# IGBT.net
KiCad netlist of a schematic drawn in Altium Designer
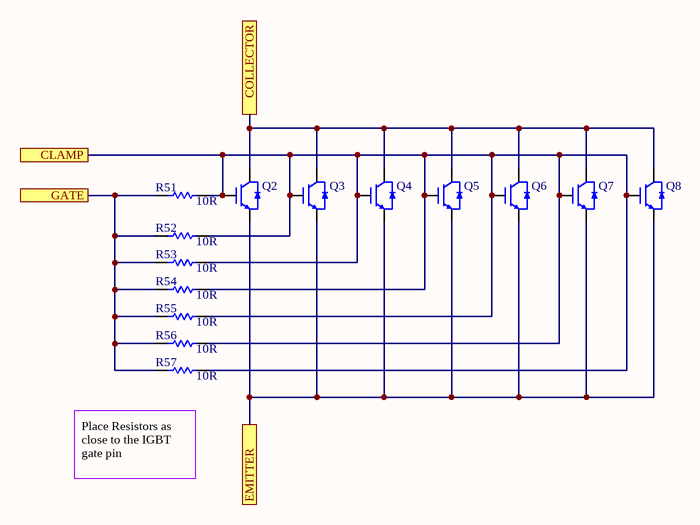
[diagram p0: IGBT.SchDoc]

(export (version "E")
  (design (tool "Eeschema 10.0.6"))
  (components
    (comp (ref "Q2")
      (value "STGB30V60DF")
      (footprint "DPAK2_IGBT")
      (description "IGBT 600V 60A 258W D2PAK")
      (fields (field (name "MANUFACTURER") "STMicroelectronics"))
      (libsource (lib "InverterSCHLib") (part "STGB30V60DF"))
    )
    (comp (ref "Q3")
      (value "STGB30V60DF")
      (footprint "DPAK2_IGBT")
      (description "IGBT 600V 60A 258W D2PAK")
      (fields (field (name "MANUFACTURER") "STMicroelectronics"))
      (libsource (lib "InverterSCHLib") (part "STGB30V60DF"))
    )
    (comp (ref "Q4")
      (value "STGB30V60DF")
      (footprint "DPAK2_IGBT")
      (description "IGBT 600V 60A 258W D2PAK")
      (fields (field (name "MANUFACTURER") "STMicroelectronics"))
      (libsource (lib "InverterSCHLib") (part "STGB30V60DF"))
    )
    (comp (ref "Q5")
      (value "STGB30V60DF")
      (footprint "DPAK2_IGBT")
      (description "IGBT 600V 60A 258W D2PAK")
      (fields (field (name "MANUFACTURER") "STMicroelectronics"))
      (libsource (lib "InverterSCHLib") (part "STGB30V60DF"))
    )
    (comp (ref "Q6")
      (value "STGB30V60DF")
      (footprint "DPAK2_IGBT")
      (description "IGBT 600V 60A 258W D2PAK")
      (fields (field (name "MANUFACTURER") "STMicroelectronics"))
      (libsource (lib "InverterSCHLib") (part "STGB30V60DF"))
    )
    (comp (ref "Q7")
      (value "STGB30V60DF")
      (footprint "DPAK2_IGBT")
      (description "IGBT 600V 60A 258W D2PAK")
      (fields (field (name "MANUFACTURER") "STMicroelectronics"))
      (libsource (lib "InverterSCHLib") (part "STGB30V60DF"))
    )
    (comp (ref "Q8")
      (value "STGB30V60DF")
      (footprint "DPAK2_IGBT")
      (description "IGBT 600V 60A 258W D2PAK")
      (fields (field (name "MANUFACTURER") "STMicroelectronics"))
      (libsource (lib "InverterSCHLib") (part "STGB30V60DF"))
    )
    (comp (ref "R51")
      (value "10R")
      (footprint "RES-0603")
      (description "RES SMD 10 OHM 1% 1/10W 0603")
      (fields
        (field (name "MANUFACTURER") "Yageo")
        (field (name "MANUFACTURER PART NUMBER") "RC0603FR-0710RL")
      )
      (libsource (lib "InverterSCHLib") (part "0603-10R"))
    )
    (comp (ref "R52")
      (value "10R")
      (footprint "RES-0603")
      (description "RES SMD 10 OHM 1% 1/10W 0603")
      (fields
        (field (name "MANUFACTURER") "Yageo")
        (field (name "MANUFACTURER PART NUMBER") "RC0603FR-0710RL")
      )
      (libsource (lib "InverterSCHLib") (part "0603-10R"))
    )
    (comp (ref "R53")
      (value "10R")
      (footprint "RES-0603")
      (description "RES SMD 10 OHM 1% 1/10W 0603")
      (fields
        (field (name "MANUFACTURER") "Yageo")
        (field (name "MANUFACTURER PART NUMBER") "RC0603FR-0710RL")
      )
      (libsource (lib "InverterSCHLib") (part "0603-10R"))
    )
    (comp (ref "R54")
      (value "10R")
      (footprint "RES-0603")
      (description "RES SMD 10 OHM 1% 1/10W 0603")
      (fields
        (field (name "MANUFACTURER") "Yageo")
        (field (name "MANUFACTURER PART NUMBER") "RC0603FR-0710RL")
      )
      (libsource (lib "InverterSCHLib") (part "0603-10R"))
    )
    (comp (ref "R55")
      (value "10R")
      (footprint "RES-0603")
      (description "RES SMD 10 OHM 1% 1/10W 0603")
      (fields
        (field (name "MANUFACTURER") "Yageo")
        (field (name "MANUFACTURER PART NUMBER") "RC0603FR-0710RL")
      )
      (libsource (lib "InverterSCHLib") (part "0603-10R"))
    )
    (comp (ref "R56")
      (value "10R")
      (footprint "RES-0603")
      (description "RES SMD 10 OHM 1% 1/10W 0603")
      (fields
        (field (name "MANUFACTURER") "Yageo")
        (field (name "MANUFACTURER PART NUMBER") "RC0603FR-0710RL")
      )
      (libsource (lib "InverterSCHLib") (part "0603-10R"))
    )
    (comp (ref "R57")
      (value "10R")
      (footprint "RES-0603")
      (description "RES SMD 10 OHM 1% 1/10W 0603")
      (fields
        (field (name "MANUFACTURER") "Yageo")
        (field (name "MANUFACTURER PART NUMBER") "RC0603FR-0710RL")
      )
      (libsource (lib "InverterSCHLib") (part "0603-10R"))
    )
  )
  (nets
    (net (code "1") (name "/CLAMP") (class "Default")
      (node (ref "Q2") (pin "1") (pinfunction "1_1") (pintype "passive"))
      (node (ref "Q3") (pin "1") (pinfunction "1_1") (pintype "passive"))
      (node (ref "Q4") (pin "1") (pinfunction "1_1") (pintype "passive"))
      (node (ref "Q5") (pin "1") (pinfunction "1_1") (pintype "passive"))
      (node (ref "Q6") (pin "1") (pinfunction "1_1") (pintype "passive"))
      (node (ref "Q7") (pin "1") (pinfunction "1_1") (pintype "passive"))
      (node (ref "Q8") (pin "1") (pinfunction "1_1") (pintype "passive"))
      (node (ref "R51") (pin "2") (pinfunction "2_2") (pintype "passive"))
      (node (ref "R52") (pin "2") (pinfunction "2_2") (pintype "passive"))
      (node (ref "R53") (pin "2") (pinfunction "2_2") (pintype "passive"))
      (node (ref "R54") (pin "2") (pinfunction "2_2") (pintype "passive"))
      (node (ref "R55") (pin "2") (pinfunction "2_2") (pintype "passive"))
      (node (ref "R56") (pin "2") (pinfunction "2_2") (pintype "passive"))
      (node (ref "R57") (pin "2") (pinfunction "2_2") (pintype "passive"))
    )
    (net (code "2") (name "/COLLECTOR") (class "Default")
      (node (ref "Q2") (pin "2") (pinfunction "2_2") (pintype "passive"))
      (node (ref "Q3") (pin "2") (pinfunction "2_2") (pintype "passive"))
      (node (ref "Q4") (pin "2") (pinfunction "2_2") (pintype "passive"))
      (node (ref "Q5") (pin "2") (pinfunction "2_2") (pintype "passive"))
      (node (ref "Q6") (pin "2") (pinfunction "2_2") (pintype "passive"))
      (node (ref "Q7") (pin "2") (pinfunction "2_2") (pintype "passive"))
      (node (ref "Q8") (pin "2") (pinfunction "2_2") (pintype "passive"))
    )
    (net (code "3") (name "/EMITTER") (class "Default")
      (node (ref "Q2") (pin "3") (pinfunction "3_3") (pintype "passive"))
      (node (ref "Q3") (pin "3") (pinfunction "3_3") (pintype "passive"))
      (node (ref "Q4") (pin "3") (pinfunction "3_3") (pintype "passive"))
      (node (ref "Q5") (pin "3") (pinfunction "3_3") (pintype "passive"))
      (node (ref "Q6") (pin "3") (pinfunction "3_3") (pintype "passive"))
      (node (ref "Q7") (pin "3") (pinfunction "3_3") (pintype "passive"))
      (node (ref "Q8") (pin "3") (pinfunction "3_3") (pintype "passive"))
    )
    (net (code "4") (name "/GATE") (class "Default")
      (node (ref "R51") (pin "1") (pinfunction "1_1") (pintype "passive"))
      (node (ref "R52") (pin "1") (pinfunction "1_1") (pintype "passive"))
      (node (ref "R53") (pin "1") (pinfunction "1_1") (pintype "passive"))
      (node (ref "R54") (pin "1") (pinfunction "1_1") (pintype "passive"))
      (node (ref "R55") (pin "1") (pinfunction "1_1") (pintype "passive"))
      (node (ref "R56") (pin "1") (pinfunction "1_1") (pintype "passive"))
      (node (ref "R57") (pin "1") (pinfunction "1_1") (pintype "passive"))
    )
  )
)
